# Breadboard-Supply.net
KiCad netlist of a schematic drawn in EAGLE
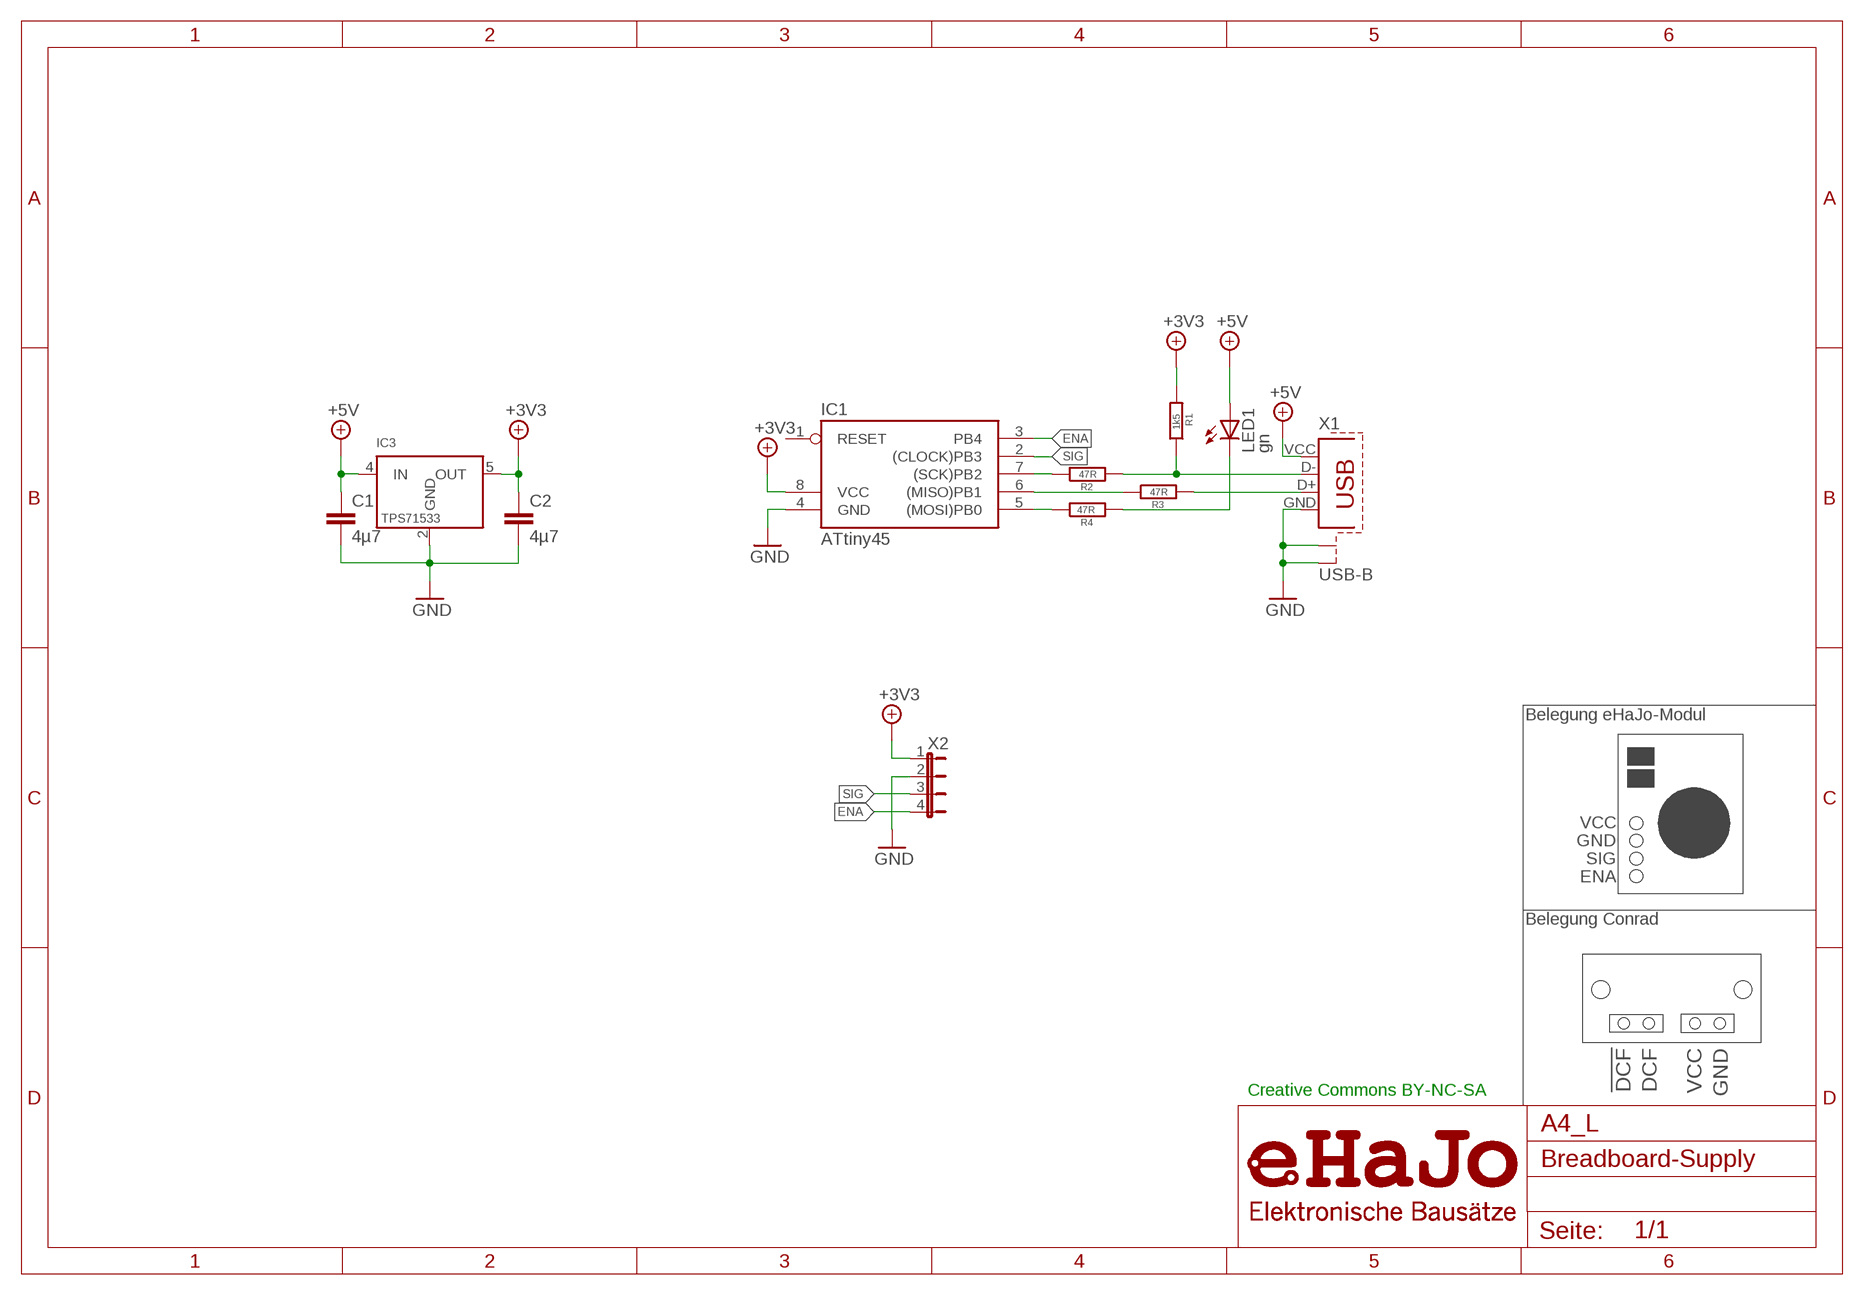
[diagram p0: schematic, sheet 1]

(export (version "E")
  (design (tool "Eeschema 10.0.6"))
  (components
    (comp (ref "C1")
      (value "4µ7")
      (footprint "eagle-import:C0805")
      (libsource (lib "eagle-import") (part "CC0805"))
    )
    (comp (ref "C2")
      (value "4µ7")
      (footprint "eagle-import:C0805")
      (libsource (lib "eagle-import") (part "CC0805"))
    )
    (comp (ref "IC1")
      (value "ATtiny45")
      (footprint "eagle-import:SOIC8")
      (libsource (lib "eagle-import") (part "TINY22S"))
    )
    (comp (ref "IC3")
      (value "TPS71533")
      (footprint "eagle-import:SOT23-DCK")
      (libsource (lib "eagle-import") (part "TPS71533"))
    )
    (comp (ref "LED1")
      (value "gn")
      (footprint "eagle-import:CHIP-LED0805")
      (libsource (lib "eagle-import") (part "LEDCHIP-LED0805"))
    )
    (comp (ref "R1")
      (value "1k5")
      (footprint "eagle-import:R0805")
      (libsource (lib "eagle-import") (part "RR0805"))
    )
    (comp (ref "R2")
      (value "47R")
      (footprint "eagle-import:R0805")
      (libsource (lib "eagle-import") (part "RR0805"))
    )
    (comp (ref "R3")
      (value "47R")
      (footprint "eagle-import:R0805")
      (libsource (lib "eagle-import") (part "RR0805"))
    )
    (comp (ref "R4")
      (value "47R")
      (footprint "eagle-import:R0805")
      (libsource (lib "eagle-import") (part "RR0805"))
    )
    (comp (ref "X1")
      (value "USB-B")
      (footprint "eagle-import:PN61729-S")
      (libsource (lib "eagle-import") (part "USB-B"))
    )
    (comp (ref "X2")
      (value "JP4E")
      (footprint "eagle-import:JP4")
      (libsource (lib "eagle-import") (part "JP4E"))
    )
  )
  (nets
    (net (code "1") (name "+3V3") (class "Default")
      (node (ref "C2") (pin "1") (pinfunction "1_1") (pintype "passive"))
      (node (ref "IC1") (pin "8") (pinfunction "VCC_8") (pintype "power_in"))
      (node (ref "IC3") (pin "5") (pinfunction "OUT_5") (pintype "power_in"))
      (node (ref "R1") (pin "2") (pinfunction "2_2") (pintype "passive"))
      (node (ref "X2") (pin "1") (pinfunction "1_1") (pintype "passive"))
    )
    (net (code "2") (name "+5V") (class "Default")
      (node (ref "C1") (pin "1") (pinfunction "1_1") (pintype "passive"))
      (node (ref "IC3") (pin "4") (pinfunction "IN_4") (pintype "power_in"))
      (node (ref "LED1") (pin "A") (pinfunction "A_A") (pintype "passive"))
      (node (ref "X1") (pin "VCC") (pinfunction "VCC_VCC") (pintype "passive"))
    )
    (net (code "3") (name "ENA") (class "Default")
      (node (ref "IC1") (pin "3") (pinfunction "PB4_3") (pintype "bidirectional"))
      (node (ref "X2") (pin "4") (pinfunction "4_4") (pintype "passive"))
    )
    (net (code "4") (name "GND") (class "Default")
      (node (ref "C1") (pin "2") (pinfunction "2_2") (pintype "passive"))
      (node (ref "C2") (pin "2") (pinfunction "2_2") (pintype "passive"))
      (node (ref "IC1") (pin "4") (pinfunction "GND_4") (pintype "power_in"))
      (node (ref "IC3") (pin "2") (pinfunction "GND_2") (pintype "power_in"))
      (node (ref "X1") (pin "GND") (pinfunction "GND_GND") (pintype "passive"))
      (node (ref "X1") (pin "S1") (pinfunction "S1_S1") (pintype "passive"))
      (node (ref "X1") (pin "S2") (pinfunction "S2_S2") (pintype "passive"))
      (node (ref "X2") (pin "2") (pinfunction "2_2") (pintype "passive"))
    )
    (net (code "5") (name "Net-(IC1-(MISO)PB1)") (class "Default")
      (node (ref "IC1") (pin "6") (pinfunction "(MISO)PB1_6") (pintype "bidirectional"))
      (node (ref "R3") (pin "1") (pinfunction "1_1") (pintype "passive"))
    )
    (net (code "6") (name "Net-(IC1-(MOSI)PB0)") (class "Default")
      (node (ref "IC1") (pin "5") (pinfunction "(MOSI)PB0_5") (pintype "bidirectional"))
      (node (ref "R4") (pin "1") (pinfunction "1_1") (pintype "passive"))
    )
    (net (code "7") (name "Net-(IC1-(SCK)PB2)") (class "Default")
      (node (ref "IC1") (pin "7") (pinfunction "(SCK)PB2_7") (pintype "bidirectional"))
      (node (ref "R2") (pin "1") (pinfunction "1_1") (pintype "passive"))
    )
    (net (code "8") (name "Net-(LED1-PadC)") (class "Default")
      (node (ref "LED1") (pin "C") (pinfunction "C_C") (pintype "passive"))
      (node (ref "R4") (pin "2") (pinfunction "2_2") (pintype "passive"))
    )
    (net (code "9") (name "Net-(R1-Pad1)") (class "Default")
      (node (ref "R1") (pin "1") (pinfunction "1_1") (pintype "passive"))
      (node (ref "R2") (pin "2") (pinfunction "2_2") (pintype "passive"))
      (node (ref "X1") (pin "D-") (pinfunction "D-_D-") (pintype "passive"))
    )
    (net (code "10") (name "Net-(R3-Pad2)") (class "Default")
      (node (ref "R3") (pin "2") (pinfunction "2_2") (pintype "passive"))
      (node (ref "X1") (pin "D+") (pinfunction "D+_D+") (pintype "passive"))
    )
    (net (code "11") (name "SIG") (class "Default")
      (node (ref "IC1") (pin "2") (pinfunction "(CLOCK)PB3_2") (pintype "bidirectional"))
      (node (ref "X2") (pin "3") (pinfunction "3_3") (pintype "passive"))
    )
    (net (code "12") (name "unconnected-(IC1-RESET-Pad1)") (class "Default")
      (node (ref "IC1") (pin "1") (pinfunction "RESET_1") (pintype "input"))
    )
  )
)
